# cv.net
KiCad netlist of a schematic drawn in EAGLE
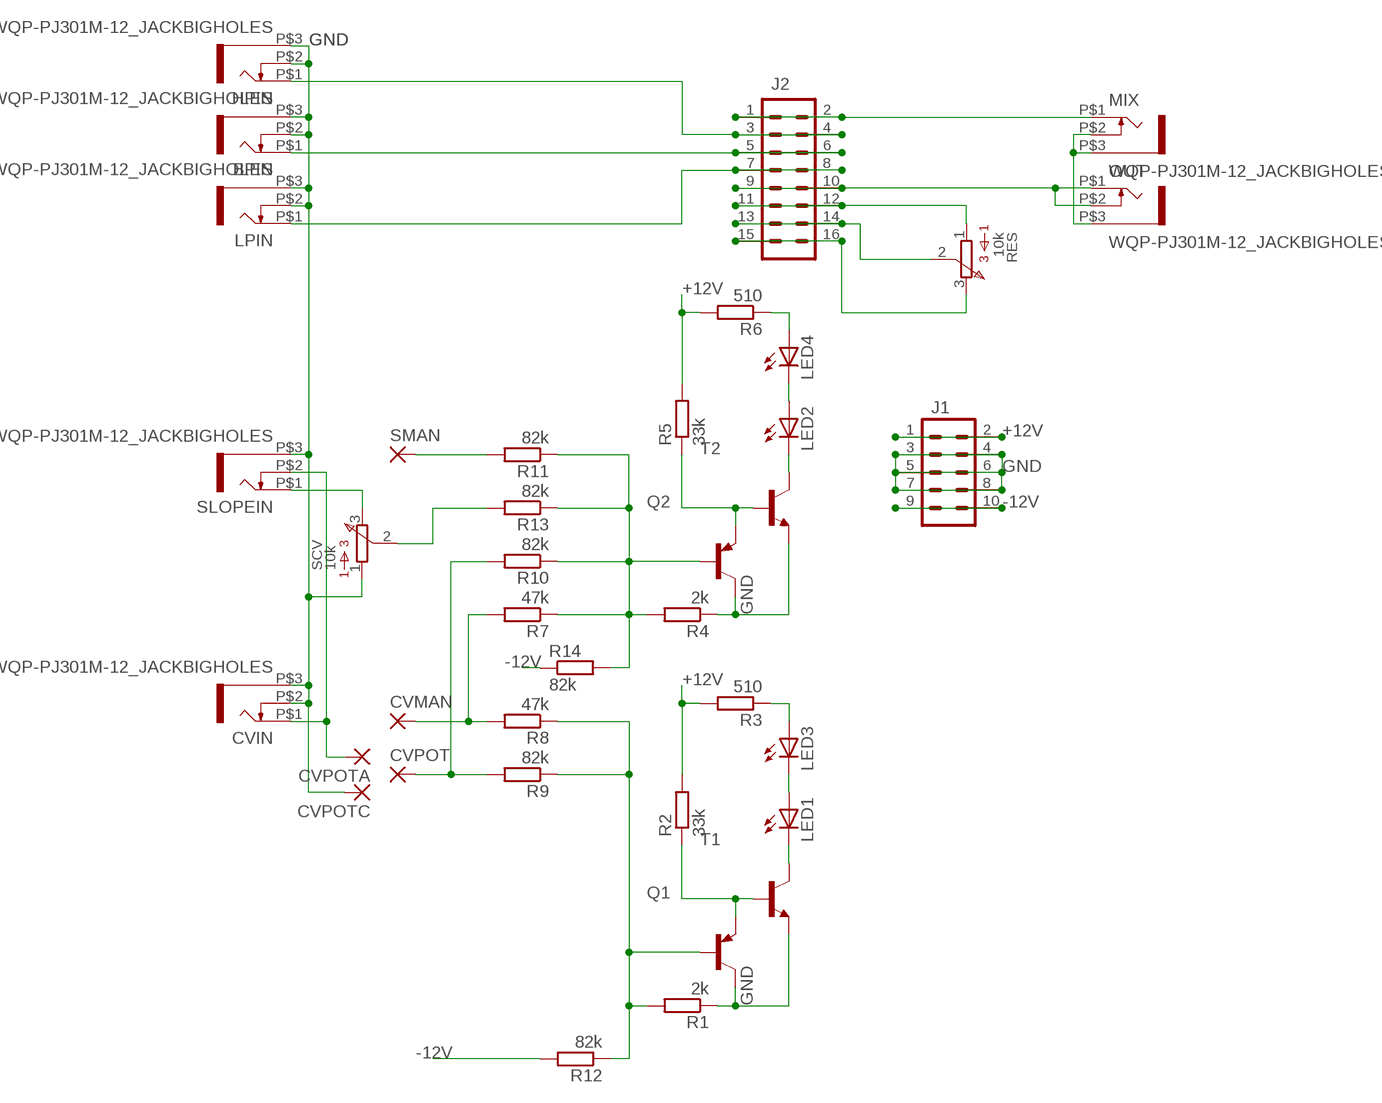
[diagram p0: schematic, sheet 1]

(export (version "E")
  (design (tool "Eeschema 10.0.6"))
  (components
    (comp (ref "BPIN")
      (value "WQP-PJ301M-12_JACKBIGHOLES")
      (footprint "eagle-import:WQP-PJ301M-12_JACK")
      (libsource (lib "eagle-import") (part "WQP-PJ301M-12_JACKBIGHOLES"))
    )
    (comp (ref "CVIN")
      (value "WQP-PJ301M-12_JACKBIGHOLES")
      (footprint "eagle-import:WQP-PJ301M-12_JACK")
      (libsource (lib "eagle-import") (part "WQP-PJ301M-12_JACKBIGHOLES"))
    )
    (comp (ref "CVMAN")
      (value "2,0/0,9-S")
      (footprint "eagle-import:2,0_0,9-S")
      (libsource (lib "eagle-import") (part "2,0/0,9-S"))
    )
    (comp (ref "CVPOT")
      (value "2,0/0,9-S")
      (footprint "eagle-import:2,0_0,9-S")
      (libsource (lib "eagle-import") (part "2,0/0,9-S"))
    )
    (comp (ref "CVPOTA")
      (value "2,0/0,9-S")
      (footprint "eagle-import:2,0_0,9-S")
      (libsource (lib "eagle-import") (part "2,0/0,9-S"))
    )
    (comp (ref "CVPOTC")
      (value "2,0/0,9-S")
      (footprint "eagle-import:2,0_0,9-S")
      (libsource (lib "eagle-import") (part "2,0/0,9-S"))
    )
    (comp (ref "HPIN")
      (value "WQP-PJ301M-12_JACKBIGHOLES")
      (footprint "eagle-import:WQP-PJ301M-12_JACK")
      (libsource (lib "eagle-import") (part "WQP-PJ301M-12_JACKBIGHOLES"))
    )
    (comp (ref "J1")
      (value "M05X2PTH")
      (footprint "eagle-import:AVR_ICSP")
      (libsource (lib "eagle-import") (part "M05X2PTH"))
    )
    (comp (ref "J2")
      (value "M08X2")
      (footprint "eagle-import:2X8")
      (libsource (lib "eagle-import") (part "M08X2"))
    )
    (comp (ref "LED1")
      (value "LEDCHIP-LED0805")
      (footprint "eagle-import:CHIP-LED0805")
      (libsource (lib "eagle-import") (part "LEDCHIP-LED0805"))
    )
    (comp (ref "LED2")
      (value "LEDCHIP-LED0805")
      (footprint "eagle-import:CHIP-LED0805")
      (libsource (lib "eagle-import") (part "LEDCHIP-LED0805"))
    )
    (comp (ref "LED3")
      (value "LED5MM")
      (footprint "eagle-import:LED5MM")
      (libsource (lib "eagle-import") (part "LED5MM"))
    )
    (comp (ref "LED4")
      (value "LED5MM")
      (footprint "eagle-import:LED5MM")
      (libsource (lib "eagle-import") (part "LED5MM"))
    )
    (comp (ref "LPIN")
      (value "WQP-PJ301M-12_JACKBIGHOLES")
      (footprint "eagle-import:WQP-PJ301M-12_JACK")
      (libsource (lib "eagle-import") (part "WQP-PJ301M-12_JACKBIGHOLES"))
    )
    (comp (ref "MIX")
      (value "WQP-PJ301M-12_JACKBIGHOLES")
      (footprint "eagle-import:WQP-PJ301M-12_JACK")
      (libsource (lib "eagle-import") (part "WQP-PJ301M-12_JACKBIGHOLES"))
    )
    (comp (ref "OUT")
      (value "WQP-PJ301M-12_JACKBIGHOLES")
      (footprint "eagle-import:WQP-PJ301M-12_JACK")
      (libsource (lib "eagle-import") (part "WQP-PJ301M-12_JACKBIGHOLES"))
    )
    (comp (ref "Q1")
      (value "MMBT3906LT1-PNP-SOT23-BEC")
      (footprint "eagle-import:SOT23-BEC")
      (libsource (lib "eagle-import") (part "-PNP-SOT23-BECMMBT3906LT1"))
    )
    (comp (ref "Q2")
      (value "MMBT3906LT1-PNP-SOT23-BEC")
      (footprint "eagle-import:SOT23-BEC")
      (libsource (lib "eagle-import") (part "-PNP-SOT23-BECMMBT3906LT1"))
    )
    (comp (ref "R1")
      (value "2k")
      (footprint "eagle-import:R1206")
      (libsource (lib "eagle-import") (part "R-EU_R1206"))
    )
    (comp (ref "R2")
      (value "33k")
      (footprint "eagle-import:R1206")
      (libsource (lib "eagle-import") (part "R-EU_R1206"))
    )
    (comp (ref "R3")
      (value "510")
      (footprint "eagle-import:R1206")
      (libsource (lib "eagle-import") (part "R-EU_R1206"))
    )
    (comp (ref "R4")
      (value "2k")
      (footprint "eagle-import:R1206")
      (libsource (lib "eagle-import") (part "R-EU_R1206"))
    )
    (comp (ref "R5")
      (value "33k")
      (footprint "eagle-import:R1206")
      (libsource (lib "eagle-import") (part "R-EU_R1206"))
    )
    (comp (ref "R6")
      (value "510")
      (footprint "eagle-import:R1206")
      (libsource (lib "eagle-import") (part "R-EU_R1206"))
    )
    (comp (ref "R7")
      (value "47k")
      (footprint "eagle-import:R1206")
      (libsource (lib "eagle-import") (part "R-EU_R1206"))
    )
    (comp (ref "R8")
      (value "47k")
      (footprint "eagle-import:R1206")
      (libsource (lib "eagle-import") (part "R-EU_R1206"))
    )
    (comp (ref "R9")
      (value "82k")
      (footprint "eagle-import:R1206")
      (libsource (lib "eagle-import") (part "R-EU_R1206"))
    )
    (comp (ref "R10")
      (value "82k")
      (footprint "eagle-import:R1206")
      (libsource (lib "eagle-import") (part "R-EU_R1206"))
    )
    (comp (ref "R11")
      (value "82k")
      (footprint "eagle-import:R1206")
      (libsource (lib "eagle-import") (part "R-EU_R1206"))
    )
    (comp (ref "R12")
      (value "82k")
      (footprint "eagle-import:R1206")
      (libsource (lib "eagle-import") (part "R-EU_R1206"))
    )
    (comp (ref "R13")
      (value "82k")
      (footprint "eagle-import:R1206")
      (libsource (lib "eagle-import") (part "R-EU_R1206"))
    )
    (comp (ref "R14")
      (value "82k")
      (footprint "eagle-import:R1206")
      (libsource (lib "eagle-import") (part "R-EU_R1206"))
    )
    (comp (ref "RES")
      (value "10k")
      (footprint "eagle-import:91")
      (libsource (lib "eagle-import") (part "91"))
    )
    (comp (ref "SCV")
      (value "10k")
      (footprint "eagle-import:91")
      (libsource (lib "eagle-import") (part "91"))
    )
    (comp (ref "SLOPEIN")
      (value "WQP-PJ301M-12_JACKBIGHOLES")
      (footprint "eagle-import:WQP-PJ301M-12_JACK")
      (libsource (lib "eagle-import") (part "WQP-PJ301M-12_JACKBIGHOLES"))
    )
    (comp (ref "SMAN")
      (value "2,0/0,9-S")
      (footprint "eagle-import:2,0_0,9-S")
      (libsource (lib "eagle-import") (part "2,0/0,9-S"))
    )
    (comp (ref "T1")
      (value "MMBT3904LT1-NPN-SOT23-BEC")
      (footprint "eagle-import:SOT23-BEC")
      (libsource (lib "eagle-import") (part "-NPN-SOT23-BECMMBT3904LT1"))
    )
    (comp (ref "T2")
      (value "MMBT3904LT1-NPN-SOT23-BEC")
      (footprint "eagle-import:SOT23-BEC")
      (libsource (lib "eagle-import") (part "-NPN-SOT23-BECMMBT3904LT1"))
    )
  )
  (nets
    (net (code "1") (name "/+12V") (class "Default")
      (node (ref "J1") (pin "1") (pinfunction "1_1") (pintype "passive"))
      (node (ref "J1") (pin "2") (pinfunction "2_2") (pintype "passive"))
      (node (ref "R2") (pin "2") (pinfunction "2_2") (pintype "passive"))
      (node (ref "R3") (pin "2") (pinfunction "2_2") (pintype "passive"))
      (node (ref "R5") (pin "2") (pinfunction "2_2") (pintype "passive"))
      (node (ref "R6") (pin "2") (pinfunction "2_2") (pintype "passive"))
    )
    (net (code "2") (name "/-12V") (class "Default")
      (node (ref "J1") (pin "10") (pinfunction "10_10") (pintype "passive"))
      (node (ref "J1") (pin "9") (pinfunction "9_9") (pintype "passive"))
      (node (ref "R12") (pin "2") (pinfunction "2_2") (pintype "passive"))
      (node (ref "R14") (pin "1") (pinfunction "1_1") (pintype "passive"))
    )
    (net (code "3") (name "/GND") (class "Default")
      (node (ref "BPIN") (pin "P$2") (pinfunction "3_P$2") (pintype "passive"))
      (node (ref "BPIN") (pin "P$3") (pinfunction "1_P$3") (pintype "passive"))
      (node (ref "CVIN") (pin "P$2") (pinfunction "3_P$2") (pintype "passive"))
      (node (ref "CVIN") (pin "P$3") (pinfunction "1_P$3") (pintype "passive"))
      (node (ref "CVPOTC") (pin "1") (pinfunction "P_1") (pintype "passive"))
      (node (ref "HPIN") (pin "P$2") (pinfunction "3_P$2") (pintype "passive"))
      (node (ref "HPIN") (pin "P$3") (pinfunction "1_P$3") (pintype "passive"))
      (node (ref "J1") (pin "3") (pinfunction "3_3") (pintype "passive"))
      (node (ref "J1") (pin "4") (pinfunction "4_4") (pintype "passive"))
      (node (ref "J1") (pin "5") (pinfunction "5_5") (pintype "passive"))
      (node (ref "J1") (pin "6") (pinfunction "6_6") (pintype "passive"))
      (node (ref "J1") (pin "7") (pinfunction "7_7") (pintype "passive"))
      (node (ref "J1") (pin "8") (pinfunction "8_8") (pintype "passive"))
      (node (ref "LPIN") (pin "P$2") (pinfunction "3_P$2") (pintype "passive"))
      (node (ref "LPIN") (pin "P$3") (pinfunction "1_P$3") (pintype "passive"))
      (node (ref "MIX") (pin "P$2") (pinfunction "3_P$2") (pintype "passive"))
      (node (ref "MIX") (pin "P$3") (pinfunction "1_P$3") (pintype "passive"))
      (node (ref "OUT") (pin "P$3") (pinfunction "1_P$3") (pintype "passive"))
      (node (ref "Q1") (pin "C") (pinfunction "C_C") (pintype "passive"))
      (node (ref "Q2") (pin "C") (pinfunction "C_C") (pintype "passive"))
      (node (ref "R1") (pin "1") (pinfunction "1_1") (pintype "passive"))
      (node (ref "R4") (pin "1") (pinfunction "1_1") (pintype "passive"))
      (node (ref "SCV") (pin "1") (pinfunction "1_1") (pintype "passive"))
      (node (ref "SLOPEIN") (pin "P$3") (pinfunction "1_P$3") (pintype "passive"))
      (node (ref "T1") (pin "E") (pinfunction "E_E") (pintype "passive"))
      (node (ref "T2") (pin "E") (pinfunction "E_E") (pintype "passive"))
    )
    (net (code "4") (name "Net-(BPIN-2)") (class "Default")
      (node (ref "BPIN") (pin "P$1") (pinfunction "2_P$1") (pintype "passive"))
      (node (ref "J2") (pin "5") (pinfunction "5_5") (pintype "passive"))
      (node (ref "J2") (pin "6") (pinfunction "6_6") (pintype "passive"))
    )
    (net (code "5") (name "Net-(CVIN-2)") (class "Default")
      (node (ref "CVIN") (pin "P$1") (pinfunction "2_P$1") (pintype "passive"))
      (node (ref "CVPOTA") (pin "1") (pinfunction "P_1") (pintype "passive"))
      (node (ref "SLOPEIN") (pin "P$2") (pinfunction "3_P$2") (pintype "passive"))
    )
    (net (code "6") (name "Net-(CVMAN-P)") (class "Default")
      (node (ref "CVMAN") (pin "1") (pinfunction "P_1") (pintype "passive"))
      (node (ref "R7") (pin "2") (pinfunction "2_2") (pintype "passive"))
      (node (ref "R8") (pin "2") (pinfunction "2_2") (pintype "passive"))
    )
    (net (code "7") (name "Net-(CVPOT-P)") (class "Default")
      (node (ref "CVPOT") (pin "1") (pinfunction "P_1") (pintype "passive"))
      (node (ref "R10") (pin "2") (pinfunction "2_2") (pintype "passive"))
      (node (ref "R9") (pin "2") (pinfunction "2_2") (pintype "passive"))
    )
    (net (code "8") (name "Net-(HPIN-2)") (class "Default")
      (node (ref "HPIN") (pin "P$1") (pinfunction "2_P$1") (pintype "passive"))
      (node (ref "J2") (pin "3") (pinfunction "3_3") (pintype "passive"))
      (node (ref "J2") (pin "4") (pinfunction "4_4") (pintype "passive"))
    )
    (net (code "9") (name "Net-(J2-Pad11)") (class "Default")
      (node (ref "J2") (pin "11") (pinfunction "11_11") (pintype "passive"))
      (node (ref "J2") (pin "12") (pinfunction "12_12") (pintype "passive"))
      (node (ref "RES") (pin "1") (pinfunction "1_1") (pintype "passive"))
    )
    (net (code "10") (name "Net-(J2-Pad13)") (class "Default")
      (node (ref "J2") (pin "13") (pinfunction "13_13") (pintype "passive"))
      (node (ref "J2") (pin "14") (pinfunction "14_14") (pintype "passive"))
      (node (ref "RES") (pin "2") (pinfunction "2_2") (pintype "passive"))
    )
    (net (code "11") (name "Net-(J2-Pad15)") (class "Default")
      (node (ref "J2") (pin "15") (pinfunction "15_15") (pintype "passive"))
      (node (ref "J2") (pin "16") (pinfunction "16_16") (pintype "passive"))
      (node (ref "RES") (pin "3") (pinfunction "3_3") (pintype "passive"))
    )
    (net (code "12") (name "Net-(LED1-PadC)") (class "Default")
      (node (ref "LED1") (pin "C") (pinfunction "C_C") (pintype "passive"))
      (node (ref "T1") (pin "C") (pinfunction "C_C") (pintype "passive"))
    )
    (net (code "13") (name "Net-(LED2-PadC)") (class "Default")
      (node (ref "LED2") (pin "C") (pinfunction "C_C") (pintype "passive"))
      (node (ref "T2") (pin "C") (pinfunction "C_C") (pintype "passive"))
    )
    (net (code "14") (name "Net-(LED3-C)") (class "Default")
      (node (ref "LED1") (pin "A") (pinfunction "A_A") (pintype "passive"))
      (node (ref "LED3") (pin "K") (pinfunction "C_K") (pintype "passive"))
    )
    (net (code "15") (name "Net-(LED3-PadA)") (class "Default")
      (node (ref "LED3") (pin "A") (pinfunction "A_A") (pintype "passive"))
      (node (ref "R3") (pin "1") (pinfunction "1_1") (pintype "passive"))
    )
    (net (code "16") (name "Net-(LED4-C)") (class "Default")
      (node (ref "LED2") (pin "A") (pinfunction "A_A") (pintype "passive"))
      (node (ref "LED4") (pin "K") (pinfunction "C_K") (pintype "passive"))
    )
    (net (code "17") (name "Net-(LED4-PadA)") (class "Default")
      (node (ref "LED4") (pin "A") (pinfunction "A_A") (pintype "passive"))
      (node (ref "R6") (pin "1") (pinfunction "1_1") (pintype "passive"))
    )
    (net (code "18") (name "Net-(LPIN-2)") (class "Default")
      (node (ref "J2") (pin "7") (pinfunction "7_7") (pintype "passive"))
      (node (ref "J2") (pin "8") (pinfunction "8_8") (pintype "passive"))
      (node (ref "LPIN") (pin "P$1") (pinfunction "2_P$1") (pintype "passive"))
    )
    (net (code "19") (name "Net-(MIX-2)") (class "Default")
      (node (ref "J2") (pin "1") (pinfunction "1_1") (pintype "passive"))
      (node (ref "J2") (pin "2") (pinfunction "2_2") (pintype "passive"))
      (node (ref "MIX") (pin "P$1") (pinfunction "2_P$1") (pintype "passive"))
    )
    (net (code "20") (name "Net-(OUT-2)") (class "Default")
      (node (ref "J2") (pin "10") (pinfunction "10_10") (pintype "passive"))
      (node (ref "J2") (pin "9") (pinfunction "9_9") (pintype "passive"))
      (node (ref "OUT") (pin "P$1") (pinfunction "2_P$1") (pintype "passive"))
      (node (ref "OUT") (pin "P$2") (pinfunction "3_P$2") (pintype "passive"))
    )
    (net (code "21") (name "Net-(Q1-PadB)") (class "Default")
      (node (ref "Q1") (pin "B") (pinfunction "B_B") (pintype "passive"))
      (node (ref "R1") (pin "2") (pinfunction "2_2") (pintype "passive"))
      (node (ref "R12") (pin "1") (pinfunction "1_1") (pintype "passive"))
      (node (ref "R8") (pin "1") (pinfunction "1_1") (pintype "passive"))
      (node (ref "R9") (pin "1") (pinfunction "1_1") (pintype "passive"))
    )
    (net (code "22") (name "Net-(Q1-PadE)") (class "Default")
      (node (ref "Q1") (pin "E") (pinfunction "E_E") (pintype "passive"))
      (node (ref "R2") (pin "1") (pinfunction "1_1") (pintype "passive"))
      (node (ref "T1") (pin "B") (pinfunction "B_B") (pintype "passive"))
    )
    (net (code "23") (name "Net-(Q2-PadB)") (class "Default")
      (node (ref "Q2") (pin "B") (pinfunction "B_B") (pintype "passive"))
      (node (ref "R10") (pin "1") (pinfunction "1_1") (pintype "passive"))
      (node (ref "R11") (pin "1") (pinfunction "1_1") (pintype "passive"))
      (node (ref "R13") (pin "1") (pinfunction "1_1") (pintype "passive"))
      (node (ref "R14") (pin "2") (pinfunction "2_2") (pintype "passive"))
      (node (ref "R4") (pin "2") (pinfunction "2_2") (pintype "passive"))
      (node (ref "R7") (pin "1") (pinfunction "1_1") (pintype "passive"))
    )
    (net (code "24") (name "Net-(Q2-PadE)") (class "Default")
      (node (ref "Q2") (pin "E") (pinfunction "E_E") (pintype "passive"))
      (node (ref "R5") (pin "1") (pinfunction "1_1") (pintype "passive"))
      (node (ref "T2") (pin "B") (pinfunction "B_B") (pintype "passive"))
    )
    (net (code "25") (name "Net-(R13-Pad2)") (class "Default")
      (node (ref "R13") (pin "2") (pinfunction "2_2") (pintype "passive"))
      (node (ref "SCV") (pin "2") (pinfunction "2_2") (pintype "passive"))
    )
    (net (code "26") (name "Net-(SLOPEIN-2)") (class "Default")
      (node (ref "SCV") (pin "3") (pinfunction "3_3") (pintype "passive"))
      (node (ref "SLOPEIN") (pin "P$1") (pinfunction "2_P$1") (pintype "passive"))
    )
    (net (code "27") (name "Net-(SMAN-P)") (class "Default")
      (node (ref "R11") (pin "2") (pinfunction "2_2") (pintype "passive"))
      (node (ref "SMAN") (pin "1") (pinfunction "P_1") (pintype "passive"))
    )
  )
)
